# LVDS.net
KiCad netlist of a schematic drawn in Altium Designer
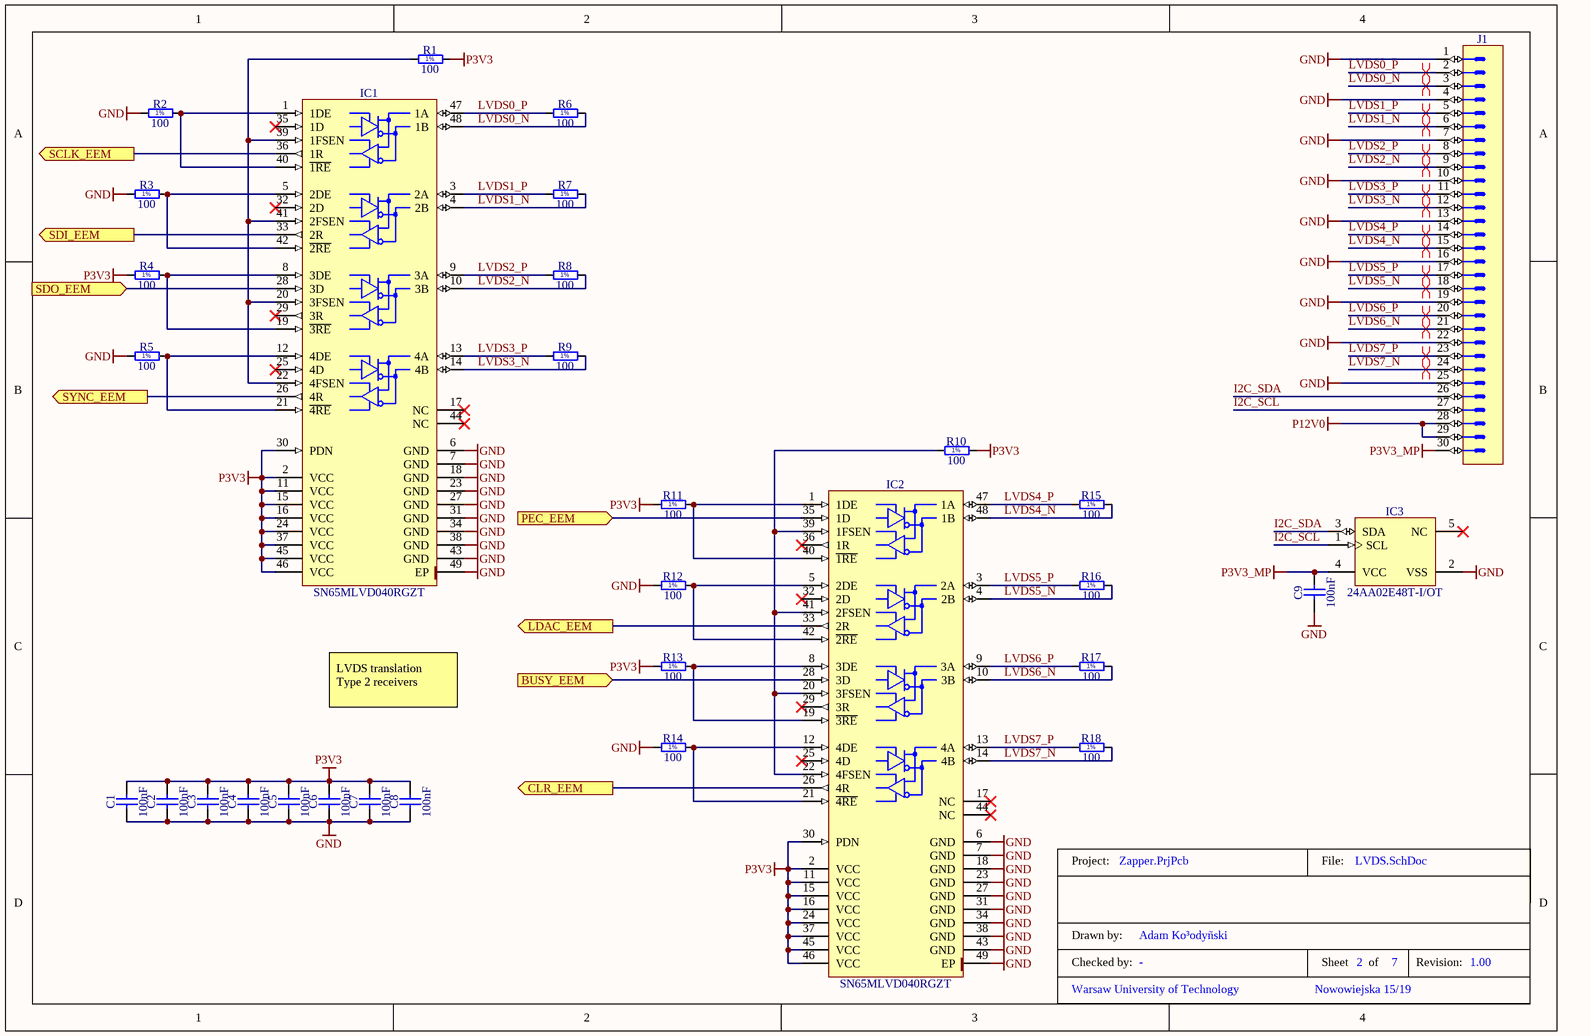
[diagram p0: LVDS.SchDoc]

(export (version "E")
  (design (tool "Eeschema 10.0.6"))
  (components
    (comp (ref "C1")
      (value "100nF")
      (footprint "CAPC1005X55N")
      (description "Non-polarised capacitor")
      (fields
        (field (name "PART NUMBER") "CC0402_100NF_16V_10%_X7R")
        (field (name "VOLTAGE") "16V")
        (field (name "AUTHOR") "CERN DEM JLC")
      )
      (libsource (lib "Capacitors") (part "Capacitor - non polarized"))
    )
    (comp (ref "C2")
      (value "100nF")
      (footprint "CAPC1005X55N")
      (description "Non-polarised capacitor")
      (fields
        (field (name "PART NUMBER") "CC0402_100NF_16V_10%_X7R")
        (field (name "VOLTAGE") "16V")
        (field (name "AUTHOR") "CERN DEM JLC")
      )
      (libsource (lib "Capacitors") (part "Capacitor - non polarized"))
    )
    (comp (ref "C3")
      (value "100nF")
      (footprint "CAPC1005X55N")
      (description "Non-polarised capacitor")
      (fields
        (field (name "PART NUMBER") "CC0402_100NF_16V_10%_X7R")
        (field (name "VOLTAGE") "16V")
        (field (name "AUTHOR") "CERN DEM JLC")
      )
      (libsource (lib "Capacitors") (part "Capacitor - non polarized"))
    )
    (comp (ref "C4")
      (value "100nF")
      (footprint "CAPC1005X55N")
      (description "Non-polarised capacitor")
      (fields
        (field (name "PART NUMBER") "CC0402_100NF_16V_10%_X7R")
        (field (name "VOLTAGE") "16V")
        (field (name "AUTHOR") "CERN DEM JLC")
      )
      (libsource (lib "Capacitors") (part "Capacitor - non polarized"))
    )
    (comp (ref "C5")
      (value "100nF")
      (footprint "CAPC1005X55N")
      (description "Non-polarised capacitor")
      (fields
        (field (name "PART NUMBER") "CC0402_100NF_16V_10%_X7R")
        (field (name "VOLTAGE") "16V")
        (field (name "AUTHOR") "CERN DEM JLC")
      )
      (libsource (lib "Capacitors") (part "Capacitor - non polarized"))
    )
    (comp (ref "C6")
      (value "100nF")
      (footprint "CAPC1005X55N")
      (description "Non-polarised capacitor")
      (fields
        (field (name "PART NUMBER") "CC0402_100NF_16V_10%_X7R")
        (field (name "VOLTAGE") "16V")
        (field (name "AUTHOR") "CERN DEM JLC")
      )
      (libsource (lib "Capacitors") (part "Capacitor - non polarized"))
    )
    (comp (ref "C7")
      (value "100nF")
      (footprint "CAPC1005X55N")
      (description "Non-polarised capacitor")
      (fields
        (field (name "PART NUMBER") "CC0402_100NF_16V_10%_X7R")
        (field (name "VOLTAGE") "16V")
        (field (name "AUTHOR") "CERN DEM JLC")
      )
      (libsource (lib "Capacitors") (part "Capacitor - non polarized"))
    )
    (comp (ref "C8")
      (value "100nF")
      (footprint "CAPC1005X55N")
      (description "Non-polarised capacitor")
      (fields
        (field (name "PART NUMBER") "CC0402_100NF_16V_10%_X7R")
        (field (name "VOLTAGE") "16V")
        (field (name "AUTHOR") "CERN DEM JLC")
      )
      (libsource (lib "Capacitors") (part "Capacitor - non polarized"))
    )
    (comp (ref "C9")
      (value "100nF")
      (footprint "CAPC1005X55N")
      (description "Non-polarised capacitor")
      (fields
        (field (name "PART NUMBER") "CC0402_100NF_16V_10%_X7R")
        (field (name "VOLTAGE") "16V")
        (field (name "AUTHOR") "CERN DEM JLC")
      )
      (libsource (lib "Capacitors") (part "Capacitor - non polarized"))
    )
    (comp (ref "IC1")
      (value "SN65MLVD040RGZT")
      (footprint "QFN50P700X700X100-49N-S420")
      (description "4-Channel Half-Duplex M-LVDS Line Transceiver")
      (fields (field (name "MANUFACTURER") "TEXAS INSTRUMENTS") (field (name "AUTHOR") "CERN DEM JLC"))
      (libsource (lib "ICs And Semiconductors") (part "SN65MLVD040"))
    )
    (comp (ref "IC2")
      (value "SN65MLVD040RGZT")
      (footprint "QFN50P700X700X100-49N-S420")
      (description "4-Channel Half-Duplex M-LVDS Line Transceiver")
      (fields (field (name "MANUFACTURER") "TEXAS INSTRUMENTS") (field (name "AUTHOR") "CERN DEM JLC"))
      (libsource (lib "ICs And Semiconductors") (part "SN65MLVD040"))
    )
    (comp (ref "IC3")
      (value "24AA02E48T-I/OT")
      (footprint "SOT95P280X145-5N")
      (description "1.7V-5.5V, 2K I2C Serial EEPROM With EUI-48 Node Identity")
      (fields (field (name "MANUFACTURER") "MICROCHIP TECHNOLOGY") (field (name "AUTHOR") "CERN DEM MR"))
      (libsource (lib "ICs And Semiconductors") (part "24AA02E48T-I/OT"))
    )
    (comp (ref "J1")
      (value "Header 30")
      (footprint "3M_N2530-6002RB")
      (description "Connector 30 Male")
      (fields
        (field (name "PART NUMBER") "3M_N2530-6002RB")
        (field (name "MANUFACTURER") "3M")
        (field (name "AUTHOR") "CERN DEM JLC")
      )
      (libsource (lib "Connectors") (part "Connector 30 Male"))
    )
    (comp (ref "R1")
      (value "100")
      (footprint "RESC1005X40N")
      (description "Resistor - 1%")
      (fields
        (field (name "PART NUMBER") "R0402_100R_1%_0.1W_100PPM")
        (field (name "POWER") "0.1W")
        (field (name "AUTHOR") "CERN DEM JLC")
      )
      (libsource (lib "Resistors") (part "Resistor - 1%"))
    )
    (comp (ref "R2")
      (value "100")
      (footprint "RESC1005X40N")
      (description "Resistor - 1%")
      (fields
        (field (name "PART NUMBER") "R0402_100R_1%_0.1W_100PPM")
        (field (name "POWER") "0.1W")
        (field (name "AUTHOR") "CERN DEM JLC")
      )
      (libsource (lib "Resistors") (part "Resistor - 1%"))
    )
    (comp (ref "R3")
      (value "100")
      (footprint "RESC1005X40N")
      (description "Resistor - 1%")
      (fields
        (field (name "PART NUMBER") "R0402_100R_1%_0.1W_100PPM")
        (field (name "POWER") "0.1W")
        (field (name "AUTHOR") "CERN DEM JLC")
      )
      (libsource (lib "Resistors") (part "Resistor - 1%"))
    )
    (comp (ref "R4")
      (value "100")
      (footprint "RESC1005X40N")
      (description "Resistor - 1%")
      (fields
        (field (name "PART NUMBER") "R0402_100R_1%_0.1W_100PPM")
        (field (name "POWER") "0.1W")
        (field (name "AUTHOR") "CERN DEM JLC")
      )
      (libsource (lib "Resistors") (part "Resistor - 1%"))
    )
    (comp (ref "R5")
      (value "100")
      (footprint "RESC1005X40N")
      (description "Resistor - 1%")
      (fields
        (field (name "PART NUMBER") "R0402_100R_1%_0.1W_100PPM")
        (field (name "POWER") "0.1W")
        (field (name "AUTHOR") "CERN DEM JLC")
      )
      (libsource (lib "Resistors") (part "Resistor - 1%"))
    )
    (comp (ref "R6")
      (value "100")
      (footprint "RESC1005X40N")
      (description "Resistor - 1%")
      (fields
        (field (name "PART NUMBER") "R0402_100R_1%_0.1W_100PPM")
        (field (name "POWER") "0.1W")
        (field (name "AUTHOR") "CERN DEM JLC")
      )
      (libsource (lib "Resistors") (part "Resistor - 1%"))
    )
    (comp (ref "R7")
      (value "100")
      (footprint "RESC1005X40N")
      (description "Resistor - 1%")
      (fields
        (field (name "PART NUMBER") "R0402_100R_1%_0.1W_100PPM")
        (field (name "POWER") "0.1W")
        (field (name "AUTHOR") "CERN DEM JLC")
      )
      (libsource (lib "Resistors") (part "Resistor - 1%"))
    )
    (comp (ref "R8")
      (value "100")
      (footprint "RESC1005X40N")
      (description "Resistor - 1%")
      (fields
        (field (name "PART NUMBER") "R0402_100R_1%_0.1W_100PPM")
        (field (name "POWER") "0.1W")
        (field (name "AUTHOR") "CERN DEM JLC")
      )
      (libsource (lib "Resistors") (part "Resistor - 1%"))
    )
    (comp (ref "R9")
      (value "100")
      (footprint "RESC1005X40N")
      (description "Resistor - 1%")
      (fields
        (field (name "PART NUMBER") "R0402_100R_1%_0.1W_100PPM")
        (field (name "POWER") "0.1W")
        (field (name "AUTHOR") "CERN DEM JLC")
      )
      (libsource (lib "Resistors") (part "Resistor - 1%"))
    )
    (comp (ref "R10")
      (value "100")
      (footprint "RESC1005X40N")
      (description "Resistor - 1%")
      (fields
        (field (name "PART NUMBER") "R0402_100R_1%_0.1W_100PPM")
        (field (name "POWER") "0.1W")
        (field (name "AUTHOR") "CERN DEM JLC")
      )
      (libsource (lib "Resistors") (part "Resistor - 1%"))
    )
    (comp (ref "R11")
      (value "100")
      (footprint "RESC1005X40N")
      (description "Resistor - 1%")
      (fields
        (field (name "PART NUMBER") "R0402_100R_1%_0.1W_100PPM")
        (field (name "POWER") "0.1W")
        (field (name "AUTHOR") "CERN DEM JLC")
      )
      (libsource (lib "Resistors") (part "Resistor - 1%"))
    )
    (comp (ref "R12")
      (value "100")
      (footprint "RESC1005X40N")
      (description "Resistor - 1%")
      (fields
        (field (name "PART NUMBER") "R0402_100R_1%_0.1W_100PPM")
        (field (name "POWER") "0.1W")
        (field (name "AUTHOR") "CERN DEM JLC")
      )
      (libsource (lib "Resistors") (part "Resistor - 1%"))
    )
    (comp (ref "R13")
      (value "100")
      (footprint "RESC1005X40N")
      (description "Resistor - 1%")
      (fields
        (field (name "PART NUMBER") "R0402_100R_1%_0.1W_100PPM")
        (field (name "POWER") "0.1W")
        (field (name "AUTHOR") "CERN DEM JLC")
      )
      (libsource (lib "Resistors") (part "Resistor - 1%"))
    )
    (comp (ref "R14")
      (value "100")
      (footprint "RESC1005X40N")
      (description "Resistor - 1%")
      (fields
        (field (name "PART NUMBER") "R0402_100R_1%_0.1W_100PPM")
        (field (name "POWER") "0.1W")
        (field (name "AUTHOR") "CERN DEM JLC")
      )
      (libsource (lib "Resistors") (part "Resistor - 1%"))
    )
    (comp (ref "R15")
      (value "100")
      (footprint "RESC1005X40N")
      (description "Resistor - 1%")
      (fields
        (field (name "PART NUMBER") "R0402_100R_1%_0.1W_100PPM")
        (field (name "POWER") "0.1W")
        (field (name "AUTHOR") "CERN DEM JLC")
      )
      (libsource (lib "Resistors") (part "Resistor - 1%"))
    )
    (comp (ref "R16")
      (value "100")
      (footprint "RESC1005X40N")
      (description "Resistor - 1%")
      (fields
        (field (name "PART NUMBER") "R0402_100R_1%_0.1W_100PPM")
        (field (name "POWER") "0.1W")
        (field (name "AUTHOR") "CERN DEM JLC")
      )
      (libsource (lib "Resistors") (part "Resistor - 1%"))
    )
    (comp (ref "R17")
      (value "100")
      (footprint "RESC1005X40N")
      (description "Resistor - 1%")
      (fields
        (field (name "PART NUMBER") "R0402_100R_1%_0.1W_100PPM")
        (field (name "POWER") "0.1W")
        (field (name "AUTHOR") "CERN DEM JLC")
      )
      (libsource (lib "Resistors") (part "Resistor - 1%"))
    )
    (comp (ref "R18")
      (value "100")
      (footprint "RESC1005X40N")
      (description "Resistor - 1%")
      (fields
        (field (name "PART NUMBER") "R0402_100R_1%_0.1W_100PPM")
        (field (name "POWER") "0.1W")
        (field (name "AUTHOR") "CERN DEM JLC")
      )
      (libsource (lib "Resistors") (part "Resistor - 1%"))
    )
    (comp (ref "TitleBlock2") (value "TitleBlock") (libsource (lib "InzLib") (part "TitleBlock")))
  )
  (nets
    (net (code "1") (name "/BUSY_EEM") (class "Default")
      (node (ref "IC2") (pin "28") (pinfunction "3D_28") (pintype "input"))
    )
    (net (code "2") (name "/CLR_EEM") (class "Default")
      (node (ref "IC2") (pin "26") (pinfunction "4R_26") (pintype "output"))
    )
    (net (code "3") (name "/I2C_SCL") (class "Default")
      (node (ref "IC3") (pin "1") (pinfunction "SCL_1") (pintype "input"))
      (node (ref "J1") (pin "27") (pinfunction "27_27") (pintype "bidirectional"))
    )
    (net (code "4") (name "/I2C_SDA") (class "Default")
      (node (ref "IC3") (pin "3") (pinfunction "SDA_3") (pintype "bidirectional"))
      (node (ref "J1") (pin "26") (pinfunction "26_26") (pintype "bidirectional"))
    )
    (net (code "5") (name "/LDAC_EEM") (class "Default")
      (node (ref "IC2") (pin "33") (pinfunction "2R_33") (pintype "output"))
    )
    (net (code "6") (name "/LVDS0_N") (class "Default")
      (node (ref "IC1") (pin "48") (pinfunction "1B_48") (pintype "bidirectional"))
      (node (ref "J1") (pin "3") (pinfunction "3_3") (pintype "bidirectional"))
      (node (ref "R6") (pin "2") (pinfunction "2_2") (pintype "passive"))
    )
    (net (code "7") (name "/LVDS0_P") (class "Default")
      (node (ref "IC1") (pin "47") (pinfunction "1A_47") (pintype "bidirectional"))
      (node (ref "J1") (pin "2") (pinfunction "2_2") (pintype "bidirectional"))
      (node (ref "R6") (pin "1") (pinfunction "1_1") (pintype "passive"))
    )
    (net (code "8") (name "/LVDS1_N") (class "Default")
      (node (ref "IC1") (pin "4") (pinfunction "2B_4") (pintype "bidirectional"))
      (node (ref "J1") (pin "6") (pinfunction "6_6") (pintype "bidirectional"))
      (node (ref "R7") (pin "2") (pinfunction "2_2") (pintype "passive"))
    )
    (net (code "9") (name "/LVDS1_P") (class "Default")
      (node (ref "IC1") (pin "3") (pinfunction "2A_3") (pintype "bidirectional"))
      (node (ref "J1") (pin "5") (pinfunction "5_5") (pintype "bidirectional"))
      (node (ref "R7") (pin "1") (pinfunction "1_1") (pintype "passive"))
    )
    (net (code "10") (name "/LVDS2_N") (class "Default")
      (node (ref "IC1") (pin "10") (pinfunction "3B_10") (pintype "bidirectional"))
      (node (ref "J1") (pin "9") (pinfunction "9_9") (pintype "bidirectional"))
      (node (ref "R8") (pin "2") (pinfunction "2_2") (pintype "passive"))
    )
    (net (code "11") (name "/LVDS2_P") (class "Default")
      (node (ref "IC1") (pin "9") (pinfunction "3A_9") (pintype "bidirectional"))
      (node (ref "J1") (pin "8") (pinfunction "8_8") (pintype "bidirectional"))
      (node (ref "R8") (pin "1") (pinfunction "1_1") (pintype "passive"))
    )
    (net (code "12") (name "/LVDS3_N") (class "Default")
      (node (ref "IC1") (pin "14") (pinfunction "4B_14") (pintype "bidirectional"))
      (node (ref "J1") (pin "12") (pinfunction "12_12") (pintype "bidirectional"))
      (node (ref "R9") (pin "2") (pinfunction "2_2") (pintype "passive"))
    )
    (net (code "13") (name "/LVDS3_P") (class "Default")
      (node (ref "IC1") (pin "13") (pinfunction "4A_13") (pintype "bidirectional"))
      (node (ref "J1") (pin "11") (pinfunction "11_11") (pintype "bidirectional"))
      (node (ref "R9") (pin "1") (pinfunction "1_1") (pintype "passive"))
    )
    (net (code "14") (name "/LVDS4_N") (class "Default")
      (node (ref "IC2") (pin "48") (pinfunction "1B_48") (pintype "bidirectional"))
      (node (ref "J1") (pin "15") (pinfunction "15_15") (pintype "bidirectional"))
      (node (ref "R15") (pin "2") (pinfunction "2_2") (pintype "passive"))
    )
    (net (code "15") (name "/LVDS4_P") (class "Default")
      (node (ref "IC2") (pin "47") (pinfunction "1A_47") (pintype "bidirectional"))
      (node (ref "J1") (pin "14") (pinfunction "14_14") (pintype "bidirectional"))
      (node (ref "R15") (pin "1") (pinfunction "1_1") (pintype "passive"))
    )
    (net (code "16") (name "/LVDS5_N") (class "Default")
      (node (ref "IC2") (pin "4") (pinfunction "2B_4") (pintype "bidirectional"))
      (node (ref "J1") (pin "18") (pinfunction "18_18") (pintype "bidirectional"))
      (node (ref "R16") (pin "2") (pinfunction "2_2") (pintype "passive"))
    )
    (net (code "17") (name "/LVDS5_P") (class "Default")
      (node (ref "IC2") (pin "3") (pinfunction "2A_3") (pintype "bidirectional"))
      (node (ref "J1") (pin "17") (pinfunction "17_17") (pintype "bidirectional"))
      (node (ref "R16") (pin "1") (pinfunction "1_1") (pintype "passive"))
    )
    (net (code "18") (name "/LVDS6_N") (class "Default")
      (node (ref "IC2") (pin "10") (pinfunction "3B_10") (pintype "bidirectional"))
      (node (ref "J1") (pin "21") (pinfunction "21_21") (pintype "bidirectional"))
      (node (ref "R17") (pin "2") (pinfunction "2_2") (pintype "passive"))
    )
    (net (code "19") (name "/LVDS6_P") (class "Default")
      (node (ref "IC2") (pin "9") (pinfunction "3A_9") (pintype "bidirectional"))
      (node (ref "J1") (pin "20") (pinfunction "20_20") (pintype "bidirectional"))
      (node (ref "R17") (pin "1") (pinfunction "1_1") (pintype "passive"))
    )
    (net (code "20") (name "/LVDS7_N") (class "Default")
      (node (ref "IC2") (pin "14") (pinfunction "4B_14") (pintype "bidirectional"))
      (node (ref "J1") (pin "24") (pinfunction "24_24") (pintype "bidirectional"))
      (node (ref "R18") (pin "2") (pinfunction "2_2") (pintype "passive"))
    )
    (net (code "21") (name "/LVDS7_P") (class "Default")
      (node (ref "IC2") (pin "13") (pinfunction "4A_13") (pintype "bidirectional"))
      (node (ref "J1") (pin "23") (pinfunction "23_23") (pintype "bidirectional"))
      (node (ref "R18") (pin "1") (pinfunction "1_1") (pintype "passive"))
    )
    (net (code "22") (name "/PEC_EEM") (class "Default")
      (node (ref "IC2") (pin "35") (pinfunction "1D_35") (pintype "input"))
    )
    (net (code "23") (name "/SCLK_EEM") (class "Default")
      (node (ref "IC1") (pin "36") (pinfunction "1R_36") (pintype "output"))
    )
    (net (code "24") (name "/SDI_EEM") (class "Default")
      (node (ref "IC1") (pin "33") (pinfunction "2R_33") (pintype "output"))
    )
    (net (code "25") (name "/SDO_EEM") (class "Default")
      (node (ref "IC1") (pin "28") (pinfunction "3D_28") (pintype "input"))
    )
    (net (code "26") (name "/SYNC_EEM") (class "Default")
      (node (ref "IC1") (pin "26") (pinfunction "4R_26") (pintype "output"))
    )
    (net (code "27") (name "GND") (class "Default")
      (node (ref "C1") (pin "1") (pinfunction "1_1") (pintype "passive"))
      (node (ref "C2") (pin "1") (pinfunction "1_1") (pintype "passive"))
      (node (ref "C3") (pin "1") (pinfunction "1_1") (pintype "passive"))
      (node (ref "C4") (pin "1") (pinfunction "1_1") (pintype "passive"))
      (node (ref "C5") (pin "1") (pinfunction "1_1") (pintype "passive"))
      (node (ref "C6") (pin "1") (pinfunction "1_1") (pintype "passive"))
      (node (ref "C7") (pin "1") (pinfunction "1_1") (pintype "passive"))
      (node (ref "C8") (pin "1") (pinfunction "1_1") (pintype "passive"))
      (node (ref "C9") (pin "1") (pinfunction "1_1") (pintype "passive"))
      (node (ref "IC1") (pin "18") (pinfunction "GND_18") (pintype "power_in"))
      (node (ref "IC1") (pin "23") (pinfunction "GND_23") (pintype "power_in"))
      (node (ref "IC1") (pin "27") (pinfunction "GND_27") (pintype "power_in"))
      (node (ref "IC1") (pin "31") (pinfunction "GND_31") (pintype "power_in"))
      (node (ref "IC1") (pin "34") (pinfunction "GND_34") (pintype "power_in"))
      (node (ref "IC1") (pin "38") (pinfunction "GND_38") (pintype "power_in"))
      (node (ref "IC1") (pin "43") (pinfunction "GND_43") (pintype "power_in"))
      (node (ref "IC1") (pin "49") (pinfunction "EP_49") (pintype "power_in"))
      (node (ref "IC1") (pin "6") (pinfunction "GND_6") (pintype "power_in"))
      (node (ref "IC1") (pin "7") (pinfunction "GND_7") (pintype "power_in"))
      (node (ref "IC2") (pin "18") (pinfunction "GND_18") (pintype "power_in"))
      (node (ref "IC2") (pin "23") (pinfunction "GND_23") (pintype "power_in"))
      (node (ref "IC2") (pin "27") (pinfunction "GND_27") (pintype "power_in"))
      (node (ref "IC2") (pin "31") (pinfunction "GND_31") (pintype "power_in"))
      (node (ref "IC2") (pin "34") (pinfunction "GND_34") (pintype "power_in"))
      (node (ref "IC2") (pin "38") (pinfunction "GND_38") (pintype "power_in"))
      (node (ref "IC2") (pin "43") (pinfunction "GND_43") (pintype "power_in"))
      (node (ref "IC2") (pin "49") (pinfunction "EP_49") (pintype "power_in"))
      (node (ref "IC2") (pin "6") (pinfunction "GND_6") (pintype "power_in"))
      (node (ref "IC2") (pin "7") (pinfunction "GND_7") (pintype "power_in"))
      (node (ref "IC3") (pin "2") (pinfunction "VSS_2") (pintype "power_in"))
      (node (ref "J1") (pin "1") (pinfunction "1_1") (pintype "bidirectional"))
      (node (ref "J1") (pin "10") (pinfunction "10_10") (pintype "bidirectional"))
      (node (ref "J1") (pin "13") (pinfunction "13_13") (pintype "bidirectional"))
      (node (ref "J1") (pin "16") (pinfunction "16_16") (pintype "bidirectional"))
      (node (ref "J1") (pin "19") (pinfunction "19_19") (pintype "bidirectional"))
      (node (ref "J1") (pin "22") (pinfunction "22_22") (pintype "bidirectional"))
      (node (ref "J1") (pin "25") (pinfunction "25_25") (pintype "bidirectional"))
      (node (ref "J1") (pin "4") (pinfunction "4_4") (pintype "bidirectional"))
      (node (ref "J1") (pin "7") (pinfunction "7_7") (pintype "bidirectional"))
      (node (ref "R12") (pin "1") (pinfunction "1_1") (pintype "passive"))
      (node (ref "R14") (pin "1") (pinfunction "1_1") (pintype "passive"))
      (node (ref "R2") (pin "1") (pinfunction "1_1") (pintype "passive"))
      (node (ref "R3") (pin "1") (pinfunction "1_1") (pintype "passive"))
      (node (ref "R5") (pin "1") (pinfunction "1_1") (pintype "passive"))
    )
    (net (code "28") (name "Net-(IC1-1DE)") (class "Default")
      (node (ref "IC1") (pin "1") (pinfunction "1DE_1") (pintype "input"))
      (node (ref "IC1") (pin "40") (pinfunction "~{1RE}_40") (pintype "input"))
      (node (ref "R2") (pin "2") (pinfunction "2_2") (pintype "passive"))
    )
    (net (code "29") (name "Net-(IC1-1FSEN)") (class "Default")
      (node (ref "IC1") (pin "20") (pinfunction "3FSEN_20") (pintype "input"))
      (node (ref "IC1") (pin "22") (pinfunction "4FSEN_22") (pintype "input"))
      (node (ref "IC1") (pin "39") (pinfunction "1FSEN_39") (pintype "input"))
      (node (ref "IC1") (pin "41") (pinfunction "2FSEN_41") (pintype "input"))
      (node (ref "R1") (pin "1") (pinfunction "1_1") (pintype "passive"))
    )
    (net (code "30") (name "Net-(IC1-2DE)") (class "Default")
      (node (ref "IC1") (pin "42") (pinfunction "~{2RE}_42") (pintype "input"))
      (node (ref "IC1") (pin "5") (pinfunction "2DE_5") (pintype "input"))
      (node (ref "R3") (pin "2") (pinfunction "2_2") (pintype "passive"))
    )
    (net (code "31") (name "Net-(IC1-3DE)") (class "Default")
      (node (ref "IC1") (pin "19") (pinfunction "~{3RE}_19") (pintype "input"))
      (node (ref "IC1") (pin "8") (pinfunction "3DE_8") (pintype "input"))
      (node (ref "R4") (pin "2") (pinfunction "2_2") (pintype "passive"))
    )
    (net (code "32") (name "Net-(IC1-4DE)") (class "Default")
      (node (ref "IC1") (pin "12") (pinfunction "4DE_12") (pintype "input"))
      (node (ref "IC1") (pin "21") (pinfunction "~{4RE}_21") (pintype "input"))
      (node (ref "R5") (pin "2") (pinfunction "2_2") (pintype "passive"))
    )
    (net (code "33") (name "Net-(IC2-1DE)") (class "Default")
      (node (ref "IC2") (pin "1") (pinfunction "1DE_1") (pintype "input"))
      (node (ref "IC2") (pin "40") (pinfunction "~{1RE}_40") (pintype "input"))
      (node (ref "R11") (pin "2") (pinfunction "2_2") (pintype "passive"))
    )
    (net (code "34") (name "Net-(IC2-1FSEN)") (class "Default")
      (node (ref "IC2") (pin "20") (pinfunction "3FSEN_20") (pintype "input"))
      (node (ref "IC2") (pin "22") (pinfunction "4FSEN_22") (pintype "input"))
      (node (ref "IC2") (pin "39") (pinfunction "1FSEN_39") (pintype "input"))
      (node (ref "IC2") (pin "41") (pinfunction "2FSEN_41") (pintype "input"))
      (node (ref "R10") (pin "1") (pinfunction "1_1") (pintype "passive"))
    )
    (net (code "35") (name "Net-(IC2-2DE)") (class "Default")
      (node (ref "IC2") (pin "42") (pinfunction "~{2RE}_42") (pintype "input"))
      (node (ref "IC2") (pin "5") (pinfunction "2DE_5") (pintype "input"))
      (node (ref "R12") (pin "2") (pinfunction "2_2") (pintype "passive"))
    )
    (net (code "36") (name "Net-(IC2-3DE)") (class "Default")
      (node (ref "IC2") (pin "19") (pinfunction "~{3RE}_19") (pintype "input"))
      (node (ref "IC2") (pin "8") (pinfunction "3DE_8") (pintype "input"))
      (node (ref "R13") (pin "2") (pinfunction "2_2") (pintype "passive"))
    )
    (net (code "37") (name "Net-(IC2-4DE)") (class "Default")
      (node (ref "IC2") (pin "12") (pinfunction "4DE_12") (pintype "input"))
      (node (ref "IC2") (pin "21") (pinfunction "~{4RE}_21") (pintype "input"))
      (node (ref "R14") (pin "2") (pinfunction "2_2") (pintype "passive"))
    )
    (net (code "38") (name "P3V3") (class "Default")
      (node (ref "C1") (pin "2") (pinfunction "2_2") (pintype "passive"))
      (node (ref "C2") (pin "2") (pinfunction "2_2") (pintype "passive"))
      (node (ref "C3") (pin "2") (pinfunction "2_2") (pintype "passive"))
      (node (ref "C4") (pin "2") (pinfunction "2_2") (pintype "passive"))
      (node (ref "C5") (pin "2") (pinfunction "2_2") (pintype "passive"))
      (node (ref "C6") (pin "2") (pinfunction "2_2") (pintype "passive"))
      (node (ref "C7") (pin "2") (pinfunction "2_2") (pintype "passive"))
      (node (ref "C8") (pin "2") (pinfunction "2_2") (pintype "passive"))
      (node (ref "IC1") (pin "11") (pinfunction "VCC_11") (pintype "power_in"))
      (node (ref "IC1") (pin "15") (pinfunction "VCC_15") (pintype "power_in"))
      (node (ref "IC1") (pin "16") (pinfunction "VCC_16") (pintype "power_in"))
      (node (ref "IC1") (pin "2") (pinfunction "VCC_2") (pintype "power_in"))
      (node (ref "IC1") (pin "24") (pinfunction "VCC_24") (pintype "power_in"))
      (node (ref "IC1") (pin "30") (pinfunction "PDN_30") (pintype "input"))
      (node (ref "IC1") (pin "37") (pinfunction "VCC_37") (pintype "power_in"))
      (node (ref "IC1") (pin "45") (pinfunction "VCC_45") (pintype "power_in"))
      (node (ref "IC1") (pin "46") (pinfunction "VCC_46") (pintype "power_in"))
      (node (ref "IC2") (pin "11") (pinfunction "VCC_11") (pintype "power_in"))
      (node (ref "IC2") (pin "15") (pinfunction "VCC_15") (pintype "power_in"))
      (node (ref "IC2") (pin "16") (pinfunction "VCC_16") (pintype "power_in"))
      (node (ref "IC2") (pin "2") (pinfunction "VCC_2") (pintype "power_in"))
      (node (ref "IC2") (pin "24") (pinfunction "VCC_24") (pintype "power_in"))
      (node (ref "IC2") (pin "30") (pinfunction "PDN_30") (pintype "input"))
      (node (ref "IC2") (pin "37") (pinfunction "VCC_37") (pintype "power_in"))
      (node (ref "IC2") (pin "45") (pinfunction "VCC_45") (pintype "power_in"))
      (node (ref "IC2") (pin "46") (pinfunction "VCC_46") (pintype "power_in"))
      (node (ref "R1") (pin "2") (pinfunction "2_2") (pintype "passive"))
      (node (ref "R10") (pin "2") (pinfunction "2_2") (pintype "passive"))
      (node (ref "R11") (pin "1") (pinfunction "1_1") (pintype "passive"))
      (node (ref "R13") (pin "1") (pinfunction "1_1") (pintype "passive"))
      (node (ref "R4") (pin "1") (pinfunction "1_1") (pintype "passive"))
    )
    (net (code "39") (name "P3V3_MP") (class "Default")
      (node (ref "C9") (pin "2") (pinfunction "2_2") (pintype "passive"))
      (node (ref "IC3") (pin "4") (pinfunction "VCC_4") (pintype "power_in"))
      (node (ref "J1") (pin "30") (pinfunction "30_30") (pintype "bidirectional"))
    )
    (net (code "40") (name "P12V0") (class "Default")
      (node (ref "J1") (pin "28") (pinfunction "28_28") (pintype "bidirectional"))
      (node (ref "J1") (pin "29") (pinfunction "29_29") (pintype "bidirectional"))
    )
    (net (code "41") (name "unconnected-(IC1-1D-Pad35)") (class "Default")
      (node (ref "IC1") (pin "35") (pinfunction "1D_35") (pintype "input+no_connect"))
    )
    (net (code "42") (name "unconnected-(IC1-2D-Pad32)") (class "Default")
      (node (ref "IC1") (pin "32") (pinfunction "2D_32") (pintype "input+no_connect"))
    )
    (net (code "43") (name "unconnected-(IC1-3R-Pad29)") (class "Default")
      (node (ref "IC1") (pin "29") (pinfunction "3R_29") (pintype "output+no_connect"))
    )
    (net (code "44") (name "unconnected-(IC1-4D-Pad25)") (class "Default")
      (node (ref "IC1") (pin "25") (pinfunction "4D_25") (pintype "input+no_connect"))
    )
    (net (code "45") (name "unconnected-(IC1-NC-Pad17)") (class "Default")
      (node (ref "IC1") (pin "17") (pinfunction "NC_17") (pintype "passive+no_connect"))
    )
    (net (code "46") (name "unconnected-(IC1-NC-Pad44)") (class "Default")
      (node (ref "IC1") (pin "44") (pinfunction "NC_44") (pintype "passive+no_connect"))
    )
    (net (code "47") (name "unconnected-(IC2-1R-Pad36)") (class "Default")
      (node (ref "IC2") (pin "36") (pinfunction "1R_36") (pintype "output+no_connect"))
    )
    (net (code "48") (name "unconnected-(IC2-2D-Pad32)") (class "Default")
      (node (ref "IC2") (pin "32") (pinfunction "2D_32") (pintype "input+no_connect"))
    )
    (net (code "49") (name "unconnected-(IC2-3R-Pad29)") (class "Default")
      (node (ref "IC2") (pin "29") (pinfunction "3R_29") (pintype "output+no_connect"))
    )
    (net (code "50") (name "unconnected-(IC2-4D-Pad25)") (class "Default")
      (node (ref "IC2") (pin "25") (pinfunction "4D_25") (pintype "input+no_connect"))
    )
    (net (code "51") (name "unconnected-(IC2-NC-Pad17)") (class "Default")
      (node (ref "IC2") (pin "17") (pinfunction "NC_17") (pintype "passive+no_connect"))
    )
    (net (code "52") (name "unconnected-(IC2-NC-Pad44)") (class "Default")
      (node (ref "IC2") (pin "44") (pinfunction "NC_44") (pintype "passive+no_connect"))
    )
    (net (code "53") (name "unconnected-(IC3-NC-Pad5)") (class "Default")
      (node (ref "IC3") (pin "5") (pinfunction "NC_5") (pintype "passive+no_connect"))
    )
  )
)
